# MIET_464512_002_E3_Sheet_1.net
KiCad netlist of a schematic drawn in Altium Designer
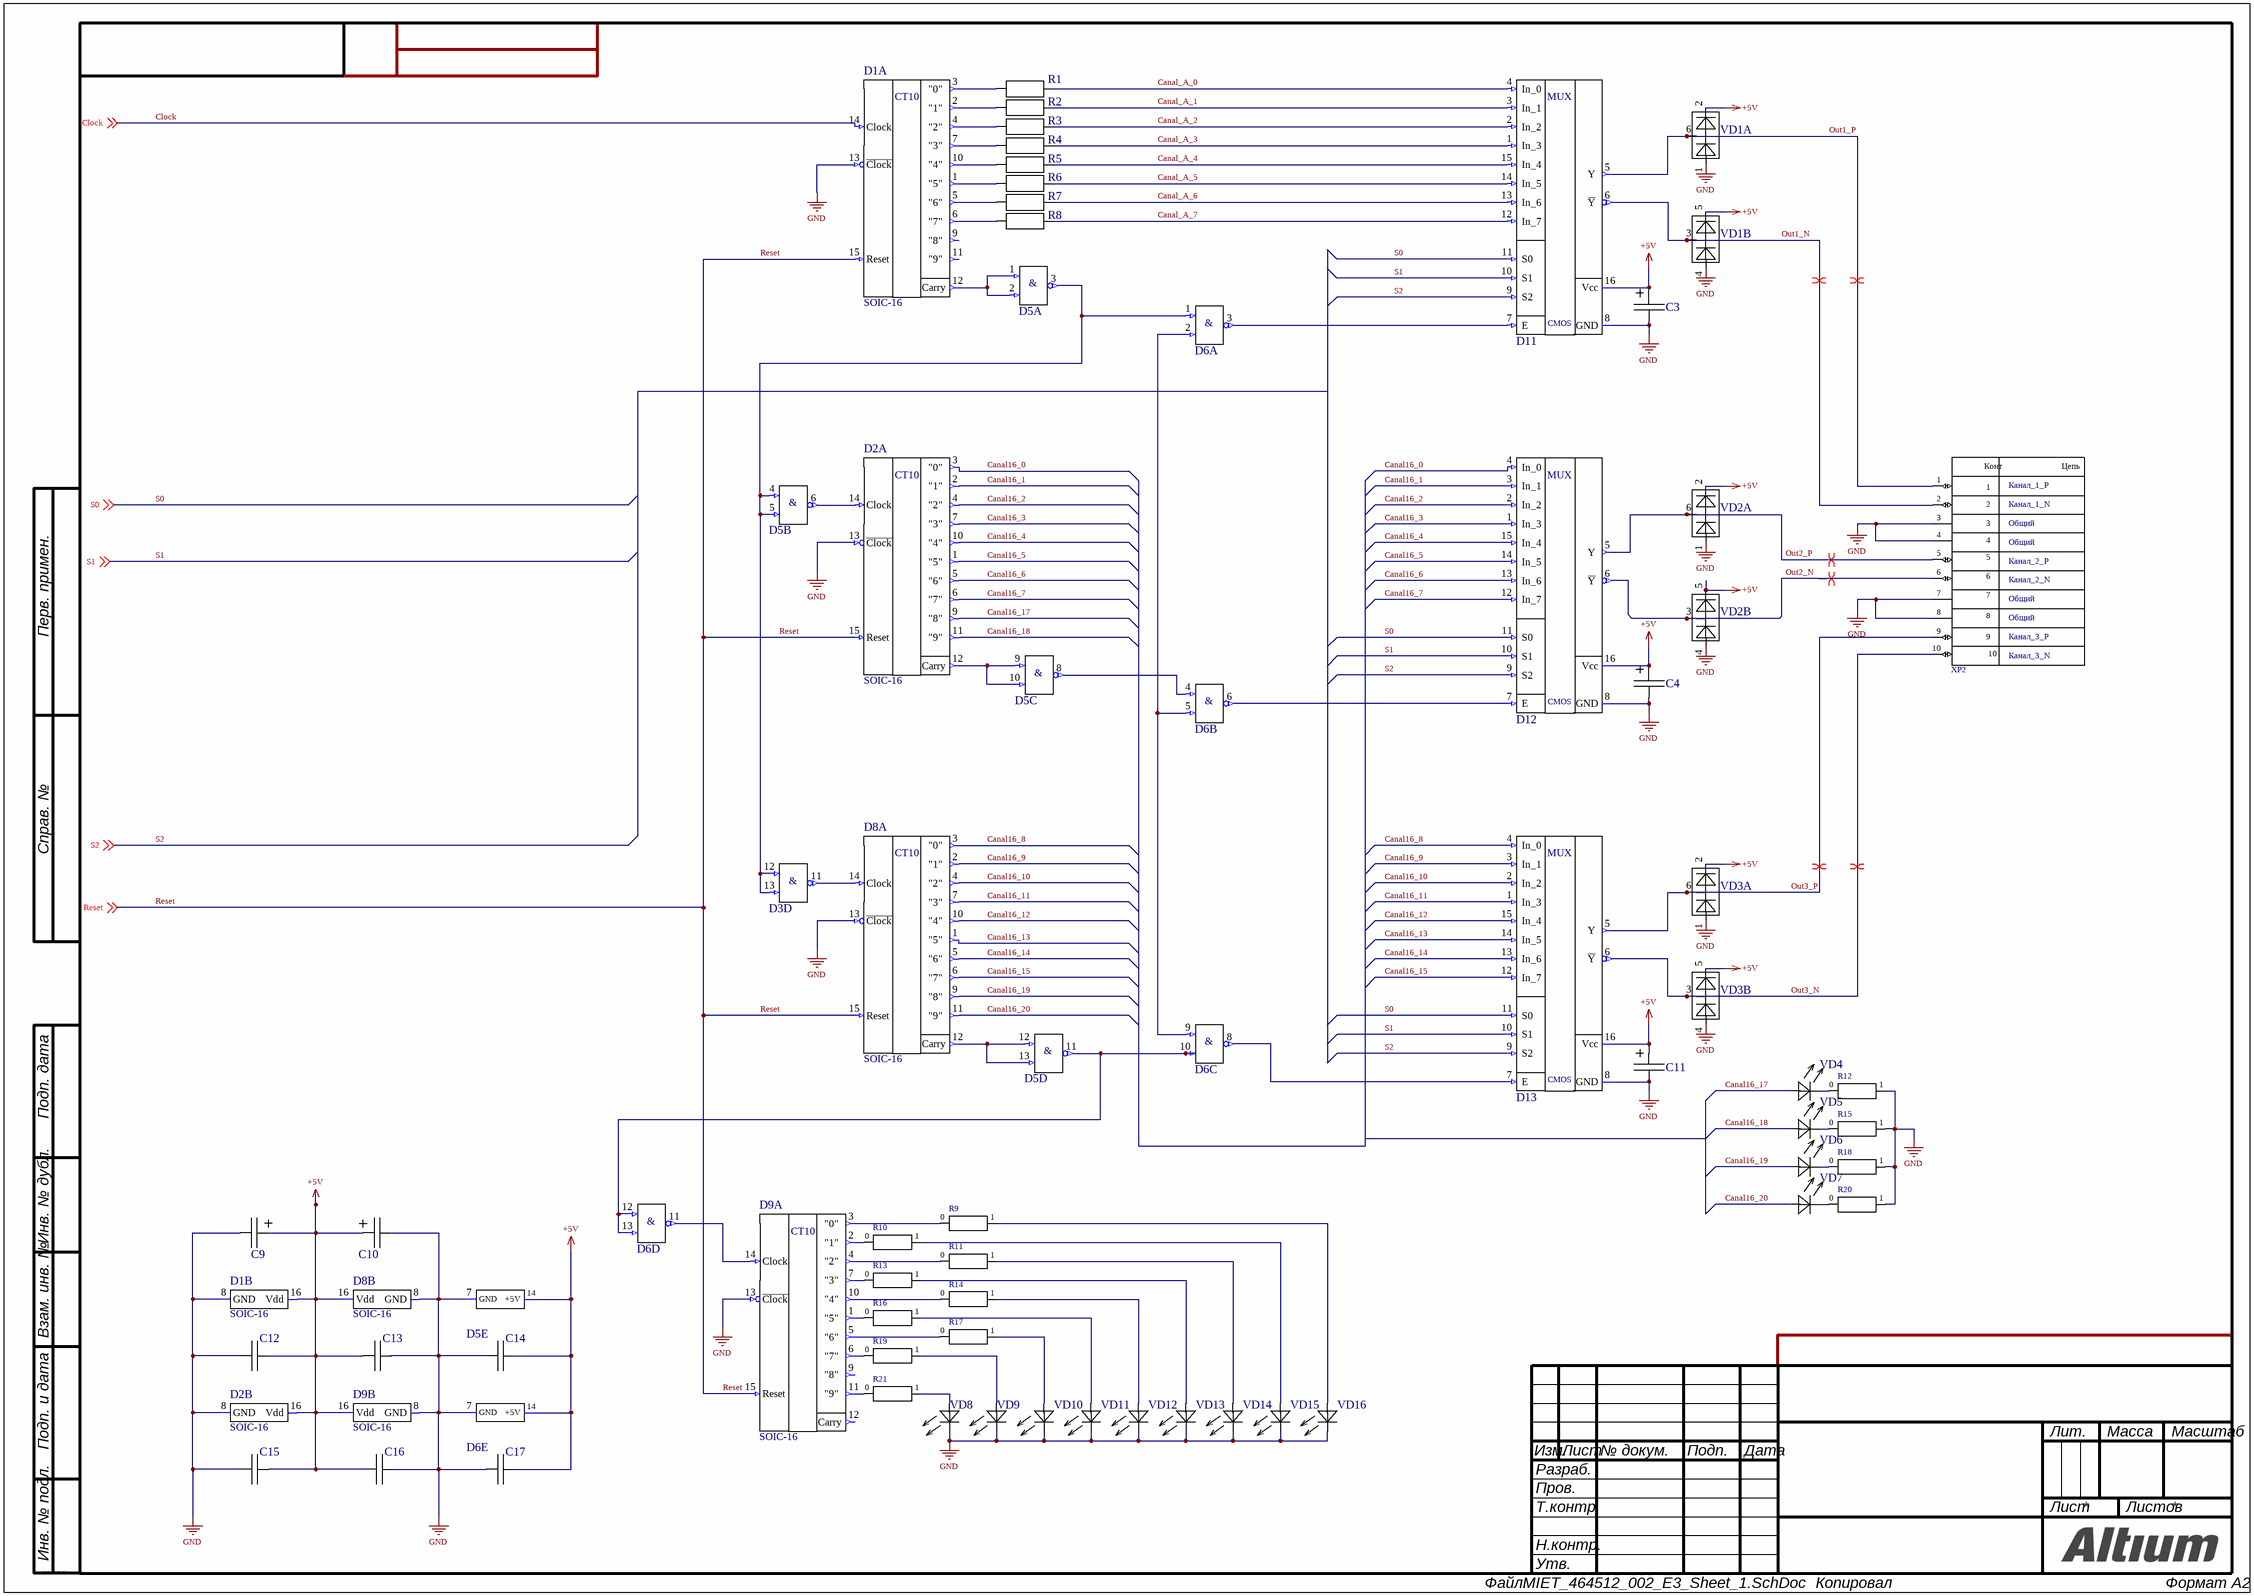
[diagram p0: MIET_464512_002_E3_Sheet_1.SchDoc]

(export (version "E")
  (design (tool "Eeschema 10.0.6"))
  (components
    (comp (ref "C3")
      (value "C")
      (footprint "C-Tantal")
      (description "К53-65 Конденсатор танталовый C(6032) 0,47-100 мкФ")
      (fields
        (field (name "MANUFACTURER") "ОАО \"Элеконд\"")
        (field (name "TOLERANCE") "10%")
        (field (name "CREATED_BY") "Желобаев")
      )
      (libsource (lib "Int_Library_for_Lessons") (part "K53-65_C_10%"))
    )
    (comp (ref "C4")
      (value "C")
      (footprint "C-Tantal")
      (description "К53-65 Конденсатор танталовый C(6032) 0,47-100 мкФ")
      (fields
        (field (name "MANUFACTURER") "ОАО \"Элеконд\"")
        (field (name "TOLERANCE") "10%")
        (field (name "CREATED_BY") "Желобаев")
      )
      (libsource (lib "Int_Library_for_Lessons") (part "K53-65_C_10%"))
    )
    (comp (ref "C9")
      (value "C")
      (footprint "C-Tantal")
      (description "К53-65 Конденсатор танталовый C(6032) 0,47-100 мкФ")
      (fields
        (field (name "MANUFACTURER") "ОАО \"Элеконд\"")
        (field (name "TOLERANCE") "10%")
        (field (name "CREATED_BY") "Желобаев")
      )
      (libsource (lib "Int_Library_for_Lessons") (part "K53-65_C_10%"))
    )
    (comp (ref "C10")
      (value "C")
      (footprint "C-Tantal")
      (description "К53-65 Конденсатор танталовый C(6032) 0,47-100 мкФ")
      (fields
        (field (name "MANUFACTURER") "ОАО \"Элеконд\"")
        (field (name "TOLERANCE") "10%")
        (field (name "CREATED_BY") "Желобаев")
      )
      (libsource (lib "Int_Library_for_Lessons") (part "K53-65_C_10%"))
    )
    (comp (ref "C11")
      (value "C")
      (footprint "C-Tantal")
      (description "К53-65 Конденсатор танталовый C(6032) 0,47-100 мкФ")
      (fields
        (field (name "MANUFACTURER") "ОАО \"Элеконд\"")
        (field (name "TOLERANCE") "10%")
        (field (name "CREATED_BY") "Желобаев")
      )
      (libsource (lib "Int_Library_for_Lessons") (part "K53-65_C_10%"))
    )
    (comp (ref "C12")
      (value "~")
      (footprint "0805_N")
      (description "Чип конденсатор 0805 Н90 ряд Е6")
      (fields
        (field (name "MANUFACTURER") "ООО \"Кулон\"")
        (field (name "TOLERANCE") "+80%-20%")
        (field (name "CREATED_BY") "Желобаев")
      )
      (libsource (lib "Int_Library_for_Lessons") (part "К10-79_0805_Н90"))
    )
    (comp (ref "C13")
      (value "~")
      (footprint "0805_N")
      (description "Чип конденсатор 0805 Н90 ряд Е6")
      (fields
        (field (name "MANUFACTURER") "ООО \"Кулон\"")
        (field (name "TOLERANCE") "+80%-20%")
        (field (name "CREATED_BY") "Желобаев")
      )
      (libsource (lib "Int_Library_for_Lessons") (part "К10-79_0805_Н90"))
    )
    (comp (ref "C14")
      (value "~")
      (footprint "0805_N")
      (description "Чип конденсатор 0805 Н90 ряд Е6")
      (fields
        (field (name "MANUFACTURER") "ООО \"Кулон\"")
        (field (name "TOLERANCE") "+80%-20%")
        (field (name "CREATED_BY") "Желобаев")
      )
      (libsource (lib "Int_Library_for_Lessons") (part "К10-79_0805_Н90"))
    )
    (comp (ref "C15")
      (value "~")
      (footprint "0805_N")
      (description "Чип конденсатор 0805 Н90 ряд Е6")
      (fields
        (field (name "MANUFACTURER") "ООО \"Кулон\"")
        (field (name "TOLERANCE") "+80%-20%")
        (field (name "CREATED_BY") "Желобаев")
      )
      (libsource (lib "Int_Library_for_Lessons") (part "К10-79_0805_Н90"))
    )
    (comp (ref "C16")
      (value "~")
      (footprint "0805_N")
      (description "Чип конденсатор 0805 Н90 ряд Е6")
      (fields
        (field (name "MANUFACTURER") "ООО \"Кулон\"")
        (field (name "TOLERANCE") "+80%-20%")
        (field (name "CREATED_BY") "Желобаев")
      )
      (libsource (lib "Int_Library_for_Lessons") (part "К10-79_0805_Н90"))
    )
    (comp (ref "C17")
      (value "~")
      (footprint "0805_N")
      (description "Чип конденсатор 0805 Н90 ряд Е6")
      (fields
        (field (name "MANUFACTURER") "ООО \"Кулон\"")
        (field (name "TOLERANCE") "+80%-20%")
        (field (name "CREATED_BY") "Желобаев")
      )
      (libsource (lib "Int_Library_for_Lessons") (part "К10-79_0805_Н90"))
    )
    (comp (ref "D1")
      (value "SOIC-16")
      (footprint "SO16-N")
      (description "Декадный счетчик c 10 декодированными выходами")
      (fields (field (name "MANUFACTURER") "STMicroelectronics") (field (name "CREATED_BY") "Желобаев"))
      (libsource (lib "Int_Library_for_Lessons") (part "HCF4017BM1"))
    )
    (comp (ref "D2")
      (value "SOIC-16")
      (footprint "SO16-N")
      (description "Декадный счетчик c 10 декодированными выходами")
      (fields (field (name "MANUFACTURER") "STMicroelectronics") (field (name "CREATED_BY") "Желобаев"))
      (libsource (lib "Int_Library_for_Lessons") (part "HCF4017BM1"))
    )
    (comp (ref "D3")
      (value "74AC00PC")
      (footprint "DIP14")
      (description "4 элемента 2И-НЕ TTL PDIP-14")
      (fields (field (name "MANUFACTURER") "ON Semiconductor") (field (name "CREATED_BY") "Желобаев"))
      (libsource (lib "Int_Library_for_Lessons") (part "74AC00PC"))
    )
    (comp (ref "D5")
      (value "74AC00PC")
      (footprint "DIP14")
      (description "4 элемента 2И-НЕ TTL PDIP-14")
      (fields (field (name "MANUFACTURER") "ON Semiconductor") (field (name "CREATED_BY") "Желобаев"))
      (libsource (lib "Int_Library_for_Lessons") (part "74AC00PC"))
    )
    (comp (ref "D6")
      (value "74AC00PC")
      (footprint "DIP14")
      (description "4 элемента 2И-НЕ TTL PDIP-14")
      (fields (field (name "MANUFACTURER") "ON Semiconductor") (field (name "CREATED_BY") "Желобаев"))
      (libsource (lib "Int_Library_for_Lessons") (part "74AC00PC"))
    )
    (comp (ref "D8")
      (value "SOIC-16")
      (footprint "SO16-N")
      (description "Декадный счетчик c 10 декодированными выходами")
      (fields (field (name "MANUFACTURER") "STMicroelectronics") (field (name "CREATED_BY") "Желобаев"))
      (libsource (lib "Int_Library_for_Lessons") (part "HCF4017BM1"))
    )
    (comp (ref "D9")
      (value "SOIC-16")
      (footprint "SO16-N")
      (description "Декадный счетчик c 10 декодированными выходами")
      (fields (field (name "MANUFACTURER") "STMicroelectronics") (field (name "CREATED_BY") "Желобаев"))
      (libsource (lib "Int_Library_for_Lessons") (part "HCF4017BM1"))
    )
    (comp (ref "D11")
      (value "DIP-16")
      (footprint "DIP16")
      (description "мультиплексор 8 канальный CMOS")
      (fields (field (name "MANUFACTURER") "NXP Semiconductors") (field (name "CREATED_BY") "Желобаев"))
      (libsource (lib "Int_Library_for_Lessons") (part "74HC151N"))
    )
    (comp (ref "D12")
      (value "DIP-16")
      (footprint "DIP16")
      (description "мультиплексор 8 канальный CMOS")
      (fields (field (name "MANUFACTURER") "NXP Semiconductors") (field (name "CREATED_BY") "Желобаев"))
      (libsource (lib "Int_Library_for_Lessons") (part "74HC151N"))
    )
    (comp (ref "D13")
      (value "DIP-16")
      (footprint "DIP16")
      (description "мультиплексор 8 канальный CMOS")
      (fields (field (name "MANUFACTURER") "NXP Semiconductors") (field (name "CREATED_BY") "Желобаев"))
      (libsource (lib "Int_Library_for_Lessons") (part "74HC151N"))
    )
    (comp (ref "R1")
      (value "0805")
      (footprint "RES_0805_2012_N")
      (description "Резистор от 0,75 Ом до 2 МОм")
      (fields
        (field (name "MANUFACTURER") "ОАО \"НПО \"Эркон\"")
        (field (name "TOLERANCE") "5%")
        (field (name "CREATED_BY") "Желобаев")
      )
      (libsource (lib "Int_Library_for_Lessons") (part "Р1-12-0,125-5%"))
    )
    (comp (ref "R2")
      (value "0805")
      (footprint "RES_0805_2012_N")
      (description "Резистор от 0,75 Ом до 2 МОм")
      (fields
        (field (name "MANUFACTURER") "ОАО \"НПО \"Эркон\"")
        (field (name "TOLERANCE") "5%")
        (field (name "CREATED_BY") "Желобаев")
      )
      (libsource (lib "Int_Library_for_Lessons") (part "Р1-12-0,125-5%"))
    )
    (comp (ref "R3")
      (value "0805")
      (footprint "RES_0805_2012_N")
      (description "Резистор от 0,75 Ом до 2 МОм")
      (fields
        (field (name "MANUFACTURER") "ОАО \"НПО \"Эркон\"")
        (field (name "TOLERANCE") "5%")
        (field (name "CREATED_BY") "Желобаев")
      )
      (libsource (lib "Int_Library_for_Lessons") (part "Р1-12-0,125-5%"))
    )
    (comp (ref "R4")
      (value "0805")
      (footprint "RES_0805_2012_N")
      (description "Резистор от 0,75 Ом до 2 МОм")
      (fields
        (field (name "MANUFACTURER") "ОАО \"НПО \"Эркон\"")
        (field (name "TOLERANCE") "5%")
        (field (name "CREATED_BY") "Желобаев")
      )
      (libsource (lib "Int_Library_for_Lessons") (part "Р1-12-0,125-5%"))
    )
    (comp (ref "R5")
      (value "0805")
      (footprint "RES_0805_2012_N")
      (description "Резистор от 0,75 Ом до 2 МОм")
      (fields
        (field (name "MANUFACTURER") "ОАО \"НПО \"Эркон\"")
        (field (name "TOLERANCE") "5%")
        (field (name "CREATED_BY") "Желобаев")
      )
      (libsource (lib "Int_Library_for_Lessons") (part "Р1-12-0,125-5%"))
    )
    (comp (ref "R6")
      (value "0805")
      (footprint "RES_0805_2012_N")
      (description "Резистор от 0,75 Ом до 2 МОм")
      (fields
        (field (name "MANUFACTURER") "ОАО \"НПО \"Эркон\"")
        (field (name "TOLERANCE") "5%")
        (field (name "CREATED_BY") "Желобаев")
      )
      (libsource (lib "Int_Library_for_Lessons") (part "Р1-12-0,125-5%"))
    )
    (comp (ref "R7")
      (value "0805")
      (footprint "RES_0805_2012_N")
      (description "Резистор от 0,75 Ом до 2 МОм")
      (fields
        (field (name "MANUFACTURER") "ОАО \"НПО \"Эркон\"")
        (field (name "TOLERANCE") "5%")
        (field (name "CREATED_BY") "Желобаев")
      )
      (libsource (lib "Int_Library_for_Lessons") (part "Р1-12-0,125-5%"))
    )
    (comp (ref "R8")
      (value "0805")
      (footprint "RES_0805_2012_N")
      (description "Резистор от 0,75 Ом до 2 МОм")
      (fields
        (field (name "MANUFACTURER") "ОАО \"НПО \"Эркон\"")
        (field (name "TOLERANCE") "5%")
        (field (name "CREATED_BY") "Желобаев")
      )
      (libsource (lib "Int_Library_for_Lessons") (part "Р1-12-0,125-5%"))
    )
    (comp (ref "R9")
      (value "P1-12-0,25-5%")
      (footprint "RES_1206")
      (description "Резистор 270 Ом M-\"A\" АЛЯР.434110.005 ТУ")
      (fields
        (field (name "MANUFACTURER") "ОАО \"КБ \"ИКАР\"\"")
        (field (name "TOLERANCE") "5%")
        (field (name "CREATED_BY") "Сарынина")
      )
      (libsource (lib "доп_элементы") (part "P1-12-0,25-5%"))
    )
    (comp (ref "R10")
      (value "P1-12-0,25-5%")
      (footprint "RES_1206")
      (description "Резистор 270 Ом M-\"A\" АЛЯР.434110.005 ТУ")
      (fields
        (field (name "MANUFACTURER") "ОАО \"КБ \"ИКАР\"\"")
        (field (name "TOLERANCE") "5%")
        (field (name "CREATED_BY") "Сарынина")
      )
      (libsource (lib "доп_элементы") (part "P1-12-0,25-5%"))
    )
    (comp (ref "R11")
      (value "P1-12-0,25-5%")
      (footprint "RES_1206")
      (description "Резистор 270 Ом M-\"A\" АЛЯР.434110.005 ТУ")
      (fields
        (field (name "MANUFACTURER") "ОАО \"КБ \"ИКАР\"\"")
        (field (name "TOLERANCE") "5%")
        (field (name "CREATED_BY") "Сарынина")
      )
      (libsource (lib "доп_элементы") (part "P1-12-0,25-5%"))
    )
    (comp (ref "R12")
      (value "P1-12-0,25-5%")
      (footprint "RES_1206")
      (description "Резистор 270 Ом M-\"A\" АЛЯР.434110.005 ТУ")
      (fields
        (field (name "MANUFACTURER") "ОАО \"КБ \"ИКАР\"\"")
        (field (name "TOLERANCE") "5%")
        (field (name "CREATED_BY") "Сарынина")
      )
      (libsource (lib "доп_элементы") (part "P1-12-0,25-5%"))
    )
    (comp (ref "R13")
      (value "P1-12-0,25-5%")
      (footprint "RES_1206")
      (description "Резистор 270 Ом M-\"A\" АЛЯР.434110.005 ТУ")
      (fields
        (field (name "MANUFACTURER") "ОАО \"КБ \"ИКАР\"\"")
        (field (name "TOLERANCE") "5%")
        (field (name "CREATED_BY") "Сарынина")
      )
      (libsource (lib "доп_элементы") (part "P1-12-0,25-5%"))
    )
    (comp (ref "R14")
      (value "P1-12-0,25-5%")
      (footprint "RES_1206")
      (description "Резистор 270 Ом M-\"A\" АЛЯР.434110.005 ТУ")
      (fields
        (field (name "MANUFACTURER") "ОАО \"КБ \"ИКАР\"\"")
        (field (name "TOLERANCE") "5%")
        (field (name "CREATED_BY") "Сарынина")
      )
      (libsource (lib "доп_элементы") (part "P1-12-0,25-5%"))
    )
    (comp (ref "R15")
      (value "P1-12-0,25-5%")
      (footprint "RES_1206")
      (description "Резистор 270 Ом M-\"A\" АЛЯР.434110.005 ТУ")
      (fields
        (field (name "MANUFACTURER") "ОАО \"КБ \"ИКАР\"\"")
        (field (name "TOLERANCE") "5%")
        (field (name "CREATED_BY") "Сарынина")
      )
      (libsource (lib "доп_элементы") (part "P1-12-0,25-5%"))
    )
    (comp (ref "R16")
      (value "P1-12-0,25-5%")
      (footprint "RES_1206")
      (description "Резистор 270 Ом M-\"A\" АЛЯР.434110.005 ТУ")
      (fields
        (field (name "MANUFACTURER") "ОАО \"КБ \"ИКАР\"\"")
        (field (name "TOLERANCE") "5%")
        (field (name "CREATED_BY") "Сарынина")
      )
      (libsource (lib "доп_элементы") (part "P1-12-0,25-5%"))
    )
    (comp (ref "R17")
      (value "P1-12-0,25-5%")
      (footprint "RES_1206")
      (description "Резистор 270 Ом M-\"A\" АЛЯР.434110.005 ТУ")
      (fields
        (field (name "MANUFACTURER") "ОАО \"КБ \"ИКАР\"\"")
        (field (name "TOLERANCE") "5%")
        (field (name "CREATED_BY") "Сарынина")
      )
      (libsource (lib "доп_элементы") (part "P1-12-0,25-5%"))
    )
    (comp (ref "R18")
      (value "P1-12-0,25-5%")
      (footprint "RES_1206")
      (description "Резистор 270 Ом M-\"A\" АЛЯР.434110.005 ТУ")
      (fields
        (field (name "MANUFACTURER") "ОАО \"КБ \"ИКАР\"\"")
        (field (name "TOLERANCE") "5%")
        (field (name "CREATED_BY") "Сарынина")
      )
      (libsource (lib "доп_элементы") (part "P1-12-0,25-5%"))
    )
    (comp (ref "R19")
      (value "P1-12-0,25-5%")
      (footprint "RES_1206")
      (description "Резистор 270 Ом M-\"A\" АЛЯР.434110.005 ТУ")
      (fields
        (field (name "MANUFACTURER") "ОАО \"КБ \"ИКАР\"\"")
        (field (name "TOLERANCE") "5%")
        (field (name "CREATED_BY") "Сарынина")
      )
      (libsource (lib "доп_элементы") (part "P1-12-0,25-5%"))
    )
    (comp (ref "R20")
      (value "P1-12-0,25-5%")
      (footprint "RES_1206")
      (description "Резистор 270 Ом M-\"A\" АЛЯР.434110.005 ТУ")
      (fields
        (field (name "MANUFACTURER") "ОАО \"КБ \"ИКАР\"\"")
        (field (name "TOLERANCE") "5%")
        (field (name "CREATED_BY") "Сарынина")
      )
      (libsource (lib "доп_элементы") (part "P1-12-0,25-5%"))
    )
    (comp (ref "R21")
      (value "P1-12-0,25-5%")
      (footprint "RES_1206")
      (description "Резистор 270 Ом M-\"A\" АЛЯР.434110.005 ТУ")
      (fields
        (field (name "MANUFACTURER") "ОАО \"КБ \"ИКАР\"\"")
        (field (name "TOLERANCE") "5%")
        (field (name "CREATED_BY") "Сарынина")
      )
      (libsource (lib "доп_элементы") (part "P1-12-0,25-5%"))
    )
    (comp (ref "VD1")
      (value "SOT-363")
      (footprint "SOT363_NXP")
      (description "Высокоскоростные, переключающие диоды")
      (fields
        (field (name "MANUFACTURER") "Nexperia")
        (field (name "VOLTAGE") "100")
        (field (name "CREATED_BY") "Желобаев")
      )
      (libsource (lib "Int_Library_for_Lessons") (part "BAV99S"))
    )
    (comp (ref "VD2")
      (value "SOT-363")
      (footprint "SOT363_NXP")
      (description "Высокоскоростные, переключающие диоды")
      (fields
        (field (name "MANUFACTURER") "Nexperia")
        (field (name "VOLTAGE") "100")
        (field (name "CREATED_BY") "Желобаев")
      )
      (libsource (lib "Int_Library_for_Lessons") (part "BAV99S"))
    )
    (comp (ref "VD3")
      (value "SOT-363")
      (footprint "SOT363_NXP")
      (description "Высокоскоростные, переключающие диоды")
      (fields
        (field (name "MANUFACTURER") "Nexperia")
        (field (name "VOLTAGE") "100")
        (field (name "CREATED_BY") "Желобаев")
      )
      (libsource (lib "Int_Library_for_Lessons") (part "BAV99S"))
    )
    (comp (ref "VD4")
      (value "0805")
      (footprint "0805_LightDiode")
      (description "светодиод 0805 зеленый")
      (fields (field (name "MANUFACTURER") "Kingbright") (field (name "CREATED_BY") "Желобаев"))
      (libsource (lib "Int_Library_for_Lessons") (part "AP2012MGC"))
    )
    (comp (ref "VD5")
      (value "0805")
      (footprint "0805_LightDiode")
      (description "светодиод 0805 зеленый")
      (fields (field (name "MANUFACTURER") "Kingbright") (field (name "CREATED_BY") "Желобаев"))
      (libsource (lib "Int_Library_for_Lessons") (part "AP2012MGC"))
    )
    (comp (ref "VD6")
      (value "0805")
      (footprint "0805_LightDiode")
      (description "светодиод 0805 зеленый")
      (fields (field (name "MANUFACTURER") "Kingbright") (field (name "CREATED_BY") "Желобаев"))
      (libsource (lib "Int_Library_for_Lessons") (part "AP2012MGC"))
    )
    (comp (ref "VD7")
      (value "0805")
      (footprint "0805_LightDiode")
      (description "светодиод 0805 зеленый")
      (fields (field (name "MANUFACTURER") "Kingbright") (field (name "CREATED_BY") "Желобаев"))
      (libsource (lib "Int_Library_for_Lessons") (part "AP2012MGC"))
    )
    (comp (ref "VD8")
      (value "0805")
      (footprint "0805_LightDiode")
      (description "светодиод 0805 красный")
      (fields (field (name "MANUFACTURER") "Kingbright") (field (name "CREATED_BY") "Желобаев"))
      (libsource (lib "Int_Library_for_Lessons") (part "AP2012EC"))
    )
    (comp (ref "VD9")
      (value "0805")
      (footprint "0805_LightDiode")
      (description "светодиод 0805 зеленый")
      (fields (field (name "MANUFACTURER") "Kingbright") (field (name "CREATED_BY") "Желобаев"))
      (libsource (lib "Int_Library_for_Lessons") (part "AP2012MGC"))
    )
    (comp (ref "VD10")
      (value "0805")
      (footprint "0805_LightDiode")
      (description "светодиод 0805 зеленый")
      (fields (field (name "MANUFACTURER") "Kingbright") (field (name "CREATED_BY") "Желобаев"))
      (libsource (lib "Int_Library_for_Lessons") (part "AP2012MGC"))
    )
    (comp (ref "VD11")
      (value "0805")
      (footprint "0805_LightDiode")
      (description "светодиод 0805 зеленый")
      (fields (field (name "MANUFACTURER") "Kingbright") (field (name "CREATED_BY") "Желобаев"))
      (libsource (lib "Int_Library_for_Lessons") (part "AP2012MGC"))
    )
    (comp (ref "VD12")
      (value "0805")
      (footprint "0805_LightDiode")
      (description "светодиод 0805 зеленый")
      (fields (field (name "MANUFACTURER") "Kingbright") (field (name "CREATED_BY") "Желобаев"))
      (libsource (lib "Int_Library_for_Lessons") (part "AP2012MGC"))
    )
    (comp (ref "VD13")
      (value "0805")
      (footprint "0805_LightDiode")
      (description "светодиод 0805 зеленый")
      (fields (field (name "MANUFACTURER") "Kingbright") (field (name "CREATED_BY") "Желобаев"))
      (libsource (lib "Int_Library_for_Lessons") (part "AP2012MGC"))
    )
    (comp (ref "VD14")
      (value "0805")
      (footprint "0805_LightDiode")
      (description "светодиод 0805 зеленый")
      (fields (field (name "MANUFACTURER") "Kingbright") (field (name "CREATED_BY") "Желобаев"))
      (libsource (lib "Int_Library_for_Lessons") (part "AP2012MGC"))
    )
    (comp (ref "VD15")
      (value "0805")
      (footprint "0805_LightDiode")
      (description "светодиод 0805 зеленый")
      (fields (field (name "MANUFACTURER") "Kingbright") (field (name "CREATED_BY") "Желобаев"))
      (libsource (lib "Int_Library_for_Lessons") (part "AP2012MGC"))
    )
    (comp (ref "VD16")
      (value "0805")
      (footprint "0805_LightDiode")
      (description "светодиод 0805 зеленый")
      (fields (field (name "MANUFACTURER") "Kingbright") (field (name "CREATED_BY") "Желобаев"))
      (libsource (lib "Int_Library_for_Lessons") (part "AP2012MGC"))
    )
    (comp (ref "XP2")
      (value "TE_1-1634688-0 \"TE Connectivity\"")
      (footprint "TE_1-1634688-0_IDC10_V")
      (description "Вилка прямая")
      (libsource (lib "доп_элементы") (part "TE_1-1634688-0 {dblquote}TE Connectivity{dblquote}"))
    )
  )
  (nets
    (net (code "1") (name "+5V") (class "Default")
      (node (ref "C10") (pin "+") (pinfunction "+_+") (pintype "passive"))
      (node (ref "C11") (pin "+") (pinfunction "+_+") (pintype "passive"))
      (node (ref "C12") (pin "2") (pinfunction "2_2") (pintype "passive"))
      (node (ref "C13") (pin "1") (pinfunction "1_1") (pintype "passive"))
      (node (ref "C14") (pin "2") (pinfunction "2_2") (pintype "passive"))
      (node (ref "C15") (pin "2") (pinfunction "2_2") (pintype "passive"))
      (node (ref "C16") (pin "1") (pinfunction "1_1") (pintype "passive"))
      (node (ref "C17") (pin "2") (pinfunction "2_2") (pintype "passive"))
      (node (ref "C3") (pin "+") (pinfunction "+_+") (pintype "passive"))
      (node (ref "C4") (pin "+") (pinfunction "+_+") (pintype "passive"))
      (node (ref "C9") (pin "+") (pinfunction "+_+") (pintype "passive"))
      (node (ref "D1") (pin "16") (pinfunction "Vdd_16") (pintype "power_in"))
      (node (ref "D11") (pin "16") (pinfunction "Vcc_16") (pintype "power_in"))
      (node (ref "D12") (pin "16") (pinfunction "Vcc_16") (pintype "power_in"))
      (node (ref "D13") (pin "16") (pinfunction "Vcc_16") (pintype "power_in"))
      (node (ref "D2") (pin "16") (pinfunction "Vdd_16") (pintype "power_in"))
      (node (ref "D5") (pin "14") (pinfunction "+5V_14") (pintype "power_in"))
      (node (ref "D6") (pin "14") (pinfunction "+5V_14") (pintype "power_in"))
      (node (ref "D8") (pin "16") (pinfunction "Vdd_16") (pintype "power_in"))
      (node (ref "D9") (pin "16") (pinfunction "Vdd_16") (pintype "power_in"))
      (node (ref "VD1") (pin "2") (pinfunction "K2_2") (pintype "passive"))
      (node (ref "VD1") (pin "5") (pinfunction "K4_5") (pintype "passive"))
      (node (ref "VD2") (pin "2") (pinfunction "K2_2") (pintype "passive"))
      (node (ref "VD2") (pin "5") (pinfunction "K4_5") (pintype "passive"))
      (node (ref "VD3") (pin "2") (pinfunction "K2_2") (pintype "passive"))
      (node (ref "VD3") (pin "5") (pinfunction "K4_5") (pintype "passive"))
    )
    (net (code "2") (name "/Canal16_0") (class "Default")
      (node (ref "D12") (pin "4") (pinfunction "In_0_4") (pintype "input"))
      (node (ref "D2") (pin "3") (pinfunction "\"0\"_3") (pintype "output"))
    )
    (net (code "3") (name "/Canal16_1") (class "Default")
      (node (ref "D12") (pin "3") (pinfunction "In_1_3") (pintype "input"))
      (node (ref "D2") (pin "2") (pinfunction "\"1\"_2") (pintype "output"))
    )
    (net (code "4") (name "/Canal16_2") (class "Default")
      (node (ref "D12") (pin "2") (pinfunction "In_2_2") (pintype "input"))
      (node (ref "D2") (pin "4") (pinfunction "\"2\"_4") (pintype "output"))
    )
    (net (code "5") (name "/Canal16_3") (class "Default")
      (node (ref "D12") (pin "1") (pinfunction "In_3_1") (pintype "input"))
      (node (ref "D2") (pin "7") (pinfunction "\"3\"_7") (pintype "output"))
    )
    (net (code "6") (name "/Canal16_4") (class "Default")
      (node (ref "D12") (pin "15") (pinfunction "In_4_15") (pintype "input"))
      (node (ref "D2") (pin "10") (pinfunction "\"4\"_10") (pintype "output"))
    )
    (net (code "7") (name "/Canal16_5") (class "Default")
      (node (ref "D12") (pin "14") (pinfunction "In_5_14") (pintype "input"))
      (node (ref "D2") (pin "1") (pinfunction "\"5\"_1") (pintype "output"))
    )
    (net (code "8") (name "/Canal16_6") (class "Default")
      (node (ref "D12") (pin "13") (pinfunction "In_6_13") (pintype "input"))
      (node (ref "D2") (pin "5") (pinfunction "\"6\"_5") (pintype "output"))
    )
    (net (code "9") (name "/Canal16_7") (class "Default")
      (node (ref "D12") (pin "12") (pinfunction "In_7_12") (pintype "input"))
      (node (ref "D2") (pin "6") (pinfunction "\"7\"_6") (pintype "output"))
    )
    (net (code "10") (name "/Canal16_8") (class "Default")
      (node (ref "D13") (pin "4") (pinfunction "In_0_4") (pintype "input"))
      (node (ref "D8") (pin "3") (pinfunction "\"0\"_3") (pintype "output"))
    )
    (net (code "11") (name "/Canal16_9") (class "Default")
      (node (ref "D13") (pin "3") (pinfunction "In_1_3") (pintype "input"))
      (node (ref "D8") (pin "2") (pinfunction "\"1\"_2") (pintype "output"))
    )
    (net (code "12") (name "/Canal16_10") (class "Default")
      (node (ref "D13") (pin "2") (pinfunction "In_2_2") (pintype "input"))
      (node (ref "D8") (pin "4") (pinfunction "\"2\"_4") (pintype "output"))
    )
    (net (code "13") (name "/Canal16_11") (class "Default")
      (node (ref "D13") (pin "1") (pinfunction "In_3_1") (pintype "input"))
      (node (ref "D8") (pin "7") (pinfunction "\"3\"_7") (pintype "output"))
    )
    (net (code "14") (name "/Canal16_12") (class "Default")
      (node (ref "D13") (pin "15") (pinfunction "In_4_15") (pintype "input"))
      (node (ref "D8") (pin "10") (pinfunction "\"4\"_10") (pintype "output"))
    )
    (net (code "15") (name "/Canal16_13") (class "Default")
      (node (ref "D13") (pin "14") (pinfunction "In_5_14") (pintype "input"))
      (node (ref "D8") (pin "1") (pinfunction "\"5\"_1") (pintype "output"))
    )
    (net (code "16") (name "/Canal16_14") (class "Default")
      (node (ref "D13") (pin "13") (pinfunction "In_6_13") (pintype "input"))
      (node (ref "D8") (pin "5") (pinfunction "\"6\"_5") (pintype "output"))
    )
    (net (code "17") (name "/Canal16_15") (class "Default")
      (node (ref "D13") (pin "12") (pinfunction "In_7_12") (pintype "input"))
      (node (ref "D8") (pin "6") (pinfunction "\"7\"_6") (pintype "output"))
    )
    (net (code "18") (name "/Canal16_17") (class "Default")
      (node (ref "D2") (pin "9") (pinfunction "\"8\"_9") (pintype "output"))
      (node (ref "VD4") (pin "A") (pinfunction "A_A") (pintype "passive"))
    )
    (net (code "19") (name "/Canal16_18") (class "Default")
      (node (ref "D2") (pin "11") (pinfunction "\"9\"_11") (pintype "output"))
      (node (ref "VD5") (pin "A") (pinfunction "A_A") (pintype "passive"))
    )
    (net (code "20") (name "/Canal16_19") (class "Default")
      (node (ref "D8") (pin "9") (pinfunction "\"8\"_9") (pintype "output"))
      (node (ref "VD6") (pin "A") (pinfunction "A_A") (pintype "passive"))
    )
    (net (code "21") (name "/Canal16_20") (class "Default")
      (node (ref "D8") (pin "11") (pinfunction "\"9\"_11") (pintype "output"))
      (node (ref "VD7") (pin "A") (pinfunction "A_A") (pintype "passive"))
    )
    (net (code "22") (name "/Canal_A_0") (class "Default")
      (node (ref "D11") (pin "4") (pinfunction "In_0_4") (pintype "input"))
      (node (ref "R1") (pin "2") (pinfunction "2_2") (pintype "passive"))
    )
    (net (code "23") (name "/Canal_A_1") (class "Default")
      (node (ref "D11") (pin "3") (pinfunction "In_1_3") (pintype "input"))
      (node (ref "R2") (pin "2") (pinfunction "2_2") (pintype "passive"))
    )
    (net (code "24") (name "/Canal_A_2") (class "Default")
      (node (ref "D11") (pin "2") (pinfunction "In_2_2") (pintype "input"))
      (node (ref "R3") (pin "2") (pinfunction "2_2") (pintype "passive"))
    )
    (net (code "25") (name "/Canal_A_3") (class "Default")
      (node (ref "D11") (pin "1") (pinfunction "In_3_1") (pintype "input"))
      (node (ref "R4") (pin "2") (pinfunction "2_2") (pintype "passive"))
    )
    (net (code "26") (name "/Canal_A_4") (class "Default")
      (node (ref "D11") (pin "15") (pinfunction "In_4_15") (pintype "input"))
      (node (ref "R5") (pin "2") (pinfunction "2_2") (pintype "passive"))
    )
    (net (code "27") (name "/Canal_A_5") (class "Default")
      (node (ref "D11") (pin "14") (pinfunction "In_5_14") (pintype "input"))
      (node (ref "R6") (pin "2") (pinfunction "2_2") (pintype "passive"))
    )
    (net (code "28") (name "/Canal_A_6") (class "Default")
      (node (ref "D11") (pin "13") (pinfunction "In_6_13") (pintype "input"))
      (node (ref "R7") (pin "2") (pinfunction "2_2") (pintype "passive"))
    )
    (net (code "29") (name "/Canal_A_7") (class "Default")
      (node (ref "D11") (pin "12") (pinfunction "In_7_12") (pintype "input"))
      (node (ref "R8") (pin "2") (pinfunction "2_2") (pintype "passive"))
    )
    (net (code "30") (name "/Out1_N") (class "Default")
      (node (ref "D11") (pin "6") (pinfunction "Y_6") (pintype "output"))
      (node (ref "VD1") (pin "3") (pinfunction "K3A4_3") (pintype "passive"))
      (node (ref "XP2") (pin "2") (pinfunction "39_2") (pintype "bidirectional"))
    )
    (net (code "31") (name "/Out1_P") (class "Default")
      (node (ref "D11") (pin "5") (pinfunction "Y_5") (pintype "output"))
      (node (ref "VD1") (pin "6") (pinfunction "K1A2_6") (pintype "passive"))
      (node (ref "XP2") (pin "1") (pinfunction "38_1") (pintype "bidirectional"))
    )
    (net (code "32") (name "/Out2_N") (class "Default")
      (node (ref "D12") (pin "6") (pinfunction "Y_6") (pintype "output"))
      (node (ref "VD2") (pin "3") (pinfunction "K3A4_3") (pintype "passive"))
      (node (ref "XP2") (pin "6") (pinfunction "43_6") (pintype "bidirectional"))
    )
    (net (code "33") (name "/Out2_P") (class "Default")
      (node (ref "D12") (pin "5") (pinfunction "Y_5") (pintype "output"))
      (node (ref "VD2") (pin "6") (pinfunction "K1A2_6") (pintype "passive"))
      (node (ref "XP2") (pin "5") (pinfunction "42_5") (pintype "bidirectional"))
    )
    (net (code "34") (name "/Out3_N") (class "Default")
      (node (ref "D13") (pin "6") (pinfunction "Y_6") (pintype "output"))
      (node (ref "VD3") (pin "3") (pinfunction "K3A4_3") (pintype "passive"))
      (node (ref "XP2") (pin "10") (pinfunction "47_10") (pintype "bidirectional"))
    )
    (net (code "35") (name "/Out3_P") (class "Default")
      (node (ref "D13") (pin "5") (pinfunction "Y_5") (pintype "output"))
      (node (ref "VD3") (pin "6") (pinfunction "K1A2_6") (pintype "passive"))
      (node (ref "XP2") (pin "9") (pinfunction "46_9") (pintype "bidirectional"))
    )
    (net (code "36") (name "Clock") (class "Default")
      (node (ref "D1") (pin "14") (pinfunction "Clock_14") (pintype "input"))
    )
    (net (code "37") (name "GND") (class "Default")
      (node (ref "C10") (pin "-") (pinfunction "-_-") (pintype "passive"))
      (node (ref "C11") (pin "-") (pinfunction "-_-") (pintype "passive"))
      (node (ref "C12") (pin "1") (pinfunction "1_1") (pintype "passive"))
      (node (ref "C13") (pin "2") (pinfunction "2_2") (pintype "passive"))
      (node (ref "C14") (pin "1") (pinfunction "1_1") (pintype "passive"))
      (node (ref "C15") (pin "1") (pinfunction "1_1") (pintype "passive"))
      (node (ref "C16") (pin "2") (pinfunction "2_2") (pintype "passive"))
      (node (ref "C17") (pin "1") (pinfunction "1_1") (pintype "passive"))
      (node (ref "C3") (pin "-") (pinfunction "-_-") (pintype "passive"))
      (node (ref "C4") (pin "-") (pinfunction "-_-") (pintype "passive"))
      (node (ref "C9") (pin "-") (pinfunction "-_-") (pintype "passive"))
      (node (ref "D1") (pin "13") (pinfunction "Clock_13") (pintype "input"))
      (node (ref "D1") (pin "8") (pinfunction "GND_8") (pintype "power_in"))
      (node (ref "D11") (pin "8") (pinfunction "GND_8") (pintype "power_in"))
      (node (ref "D12") (pin "8") (pinfunction "GND_8") (pintype "power_in"))
      (node (ref "D13") (pin "8") (pinfunction "GND_8") (pintype "power_in"))
      (node (ref "D2") (pin "13") (pinfunction "Clock_13") (pintype "input"))
      (node (ref "D2") (pin "8") (pinfunction "GND_8") (pintype "power_in"))
      (node (ref "D5") (pin "7") (pinfunction "GND_7") (pintype "power_in"))
      (node (ref "D6") (pin "7") (pinfunction "GND_7") (pintype "power_in"))
      (node (ref "D8") (pin "13") (pinfunction "Clock_13") (pintype "input"))
      (node (ref "D8") (pin "8") (pinfunction "GND_8") (pintype "power_in"))
      (node (ref "D9") (pin "13") (pinfunction "Clock_13") (pintype "input"))
      (node (ref "D9") (pin "8") (pinfunction "GND_8") (pintype "power_in"))
      (node (ref "R12") (pin "1") (pinfunction "1_1") (pintype "passive"))
      (node (ref "R15") (pin "1") (pinfunction "1_1") (pintype "passive"))
      (node (ref "R18") (pin "1") (pinfunction "1_1") (pintype "passive"))
      (node (ref "R20") (pin "1") (pinfunction "1_1") (pintype "passive"))
      (node (ref "VD1") (pin "1") (pinfunction "A1_1") (pintype "passive"))
      (node (ref "VD1") (pin "4") (pinfunction "A3_4") (pintype "passive"))
      (node (ref "VD10") (pin "K") (pinfunction "K_K") (pintype "passive"))
      (node (ref "VD11") (pin "K") (pinfunction "K_K") (pintype "passive"))
      (node (ref "VD12") (pin "K") (pinfunction "K_K") (pintype "passive"))
      (node (ref "VD13") (pin "K") (pinfunction "K_K") (pintype "passive"))
      (node (ref "VD14") (pin "K") (pinfunction "K_K") (pintype "passive"))
      (node (ref "VD15") (pin "K") (pinfunction "K_K") (pintype "passive"))
      (node (ref "VD16") (pin "K") (pinfunction "K_K") (pintype "passive"))
      (node (ref "VD2") (pin "1") (pinfunction "A1_1") (pintype "passive"))
      (node (ref "VD2") (pin "4") (pinfunction "A3_4") (pintype "passive"))
      (node (ref "VD3") (pin "1") (pinfunction "A1_1") (pintype "passive"))
      (node (ref "VD3") (pin "4") (pinfunction "A3_4") (pintype "passive"))
      (node (ref "VD8") (pin "K") (pinfunction "K_K") (pintype "passive"))
      (node (ref "VD9") (pin "K") (pinfunction "K_K") (pintype "passive"))
      (node (ref "XP2") (pin "3") (pinfunction "40_3") (pintype "passive"))
      (node (ref "XP2") (pin "4") (pinfunction "41_4") (pintype "passive"))
      (node (ref "XP2") (pin "7") (pinfunction "44_7") (pintype "passive"))
      (node (ref "XP2") (pin "8") (pinfunction "45_8") (pintype "passive"))
    )
    (net (code "38") (name "Net-(D1A-\"0\")") (class "Default")
      (node (ref "D1") (pin "3") (pinfunction "\"0\"_3") (pintype "output"))
      (node (ref "R1") (pin "1") (pinfunction "1_1") (pintype "passive"))
    )
    (net (code "39") (name "Net-(D1A-\"1\")") (class "Default")
      (node (ref "D1") (pin "2") (pinfunction "\"1\"_2") (pintype "output"))
      (node (ref "R2") (pin "1") (pinfunction "1_1") (pintype "passive"))
    )
    (net (code "40") (name "Net-(D1A-\"2\")") (class "Default")
      (node (ref "D1") (pin "4") (pinfunction "\"2\"_4") (pintype "output"))
      (node (ref "R3") (pin "1") (pinfunction "1_1") (pintype "passive"))
    )
    (net (code "41") (name "Net-(D1A-\"3\")") (class "Default")
      (node (ref "D1") (pin "7") (pinfunction "\"3\"_7") (pintype "output"))
      (node (ref "R4") (pin "1") (pinfunction "1_1") (pintype "passive"))
    )
    (net (code "42") (name "Net-(D1A-\"4\")") (class "Default")
      (node (ref "D1") (pin "10") (pinfunction "\"4\"_10") (pintype "output"))
      (node (ref "R5") (pin "1") (pinfunction "1_1") (pintype "passive"))
    )
    (net (code "43") (name "Net-(D1A-\"5\")") (class "Default")
      (node (ref "D1") (pin "1") (pinfunction "\"5\"_1") (pintype "output"))
      (node (ref "R6") (pin "1") (pinfunction "1_1") (pintype "passive"))
    )
    (net (code "44") (name "Net-(D1A-\"6\")") (class "Default")
      (node (ref "D1") (pin "5") (pinfunction "\"6\"_5") (pintype "output"))
      (node (ref "R7") (pin "1") (pinfunction "1_1") (pintype "passive"))
    )
    (net (code "45") (name "Net-(D1A-\"7\")") (class "Default")
      (node (ref "D1") (pin "6") (pinfunction "\"7\"_6") (pintype "output"))
      (node (ref "R8") (pin "1") (pinfunction "1_1") (pintype "passive"))
    )
    (net (code "46") (name "Net-(D1A-Carry)") (class "Default")
      (node (ref "D1") (pin "12") (pinfunction "Carry_12") (pintype "output"))
      (node (ref "D5") (pin "1") (pinfunction "In1_1") (pintype "input"))
      (node (ref "D5") (pin "2") (pinfunction "In2_2") (pintype "input"))
    )
    (net (code "47") (name "Net-(D2A-Carry)") (class "Default")
      (node (ref "D2") (pin "12") (pinfunction "Carry_12") (pintype "output"))
      (node (ref "D5") (pin "10") (pinfunction "In2_10") (pintype "input"))
      (node (ref "D5") (pin "9") (pinfunction "In1_9") (pintype "input"))
    )
    (net (code "48") (name "Net-(D3D-In1)") (class "Default")
      (node (ref "D3") (pin "12") (pinfunction "In1_12") (pintype "input"))
      (node (ref "D3") (pin "13") (pinfunction "In2_13") (pintype "input"))
      (node (ref "D5") (pin "3") (pinfunction "Out_3") (pintype "output"))
      (node (ref "D5") (pin "4") (pinfunction "In1_4") (pintype "input"))
      (node (ref "D5") (pin "5") (pinfunction "In2_5") (pintype "input"))
      (node (ref "D6") (pin "1") (pinfunction "In1_1") (pintype "input"))
    )
    (net (code "49") (name "Net-(D3D-Out)") (class "Default")
      (node (ref "D3") (pin "11") (pinfunction "Out_11") (pintype "output"))
      (node (ref "D8") (pin "14") (pinfunction "Clock_14") (pintype "input"))
    )
    (net (code "50") (name "Net-(D5B-Out)") (class "Default")
      (node (ref "D2") (pin "14") (pinfunction "Clock_14") (pintype "input"))
      (node (ref "D5") (pin "6") (pinfunction "Out_6") (pintype "output"))
    )
    (net (code "51") (name "Net-(D5C-Out)") (class "Default")
      (node (ref "D5") (pin "8") (pinfunction "Out_8") (pintype "output"))
      (node (ref "D6") (pin "4") (pinfunction "In1_4") (pintype "input"))
    )
    (net (code "52") (name "Net-(D5D-In1)") (class "Default")
      (node (ref "D5") (pin "12") (pinfunction "In1_12") (pintype "input"))
      (node (ref "D5") (pin "13") (pinfunction "In2_13") (pintype "input"))
      (node (ref "D8") (pin "12") (pinfunction "Carry_12") (pintype "output"))
    )
    (net (code "53") (name "Net-(D5D-Out)") (class "Default")
      (node (ref "D5") (pin "11") (pinfunction "Out_11") (pintype "output"))
      (node (ref "D6") (pin "10") (pinfunction "In2_10") (pintype "input"))
      (node (ref "D6") (pin "12") (pinfunction "In1_12") (pintype "input"))
      (node (ref "D6") (pin "13") (pinfunction "In2_13") (pintype "input"))
    )
    (net (code "54") (name "Net-(D6A-In2)") (class "Default")
      (node (ref "D6") (pin "2") (pinfunction "In2_2") (pintype "input"))
      (node (ref "D6") (pin "5") (pinfunction "In2_5") (pintype "input"))
      (node (ref "D6") (pin "9") (pinfunction "In1_9") (pintype "input"))
    )
    (net (code "55") (name "Net-(D6D-Out)") (class "Default")
      (node (ref "D6") (pin "11") (pinfunction "Out_11") (pintype "output"))
      (node (ref "D9") (pin "14") (pinfunction "Clock_14") (pintype "input"))
    )
    (net (code "56") (name "Net-(D9A-\"0\")") (class "Default")
      (node (ref "D9") (pin "3") (pinfunction "\"0\"_3") (pintype "output"))
      (node (ref "R9") (pin "0") (pinfunction "1_0") (pintype "passive"))
    )
    (net (code "57") (name "Net-(D9A-\"1\")") (class "Default")
      (node (ref "D9") (pin "2") (pinfunction "\"1\"_2") (pintype "output"))
      (node (ref "R10") (pin "0") (pinfunction "1_0") (pintype "passive"))
    )
    (net (code "58") (name "Net-(D9A-\"2\")") (class "Default")
      (node (ref "D9") (pin "4") (pinfunction "\"2\"_4") (pintype "output"))
      (node (ref "R11") (pin "0") (pinfunction "1_0") (pintype "passive"))
    )
    (net (code "59") (name "Net-(D9A-\"3\")") (class "Default")
      (node (ref "D9") (pin "7") (pinfunction "\"3\"_7") (pintype "output"))
      (node (ref "R13") (pin "0") (pinfunction "1_0") (pintype "passive"))
    )
    (net (code "60") (name "Net-(D9A-\"4\")") (class "Default")
      (node (ref "D9") (pin "10") (pinfunction "\"4\"_10") (pintype "output"))
      (node (ref "R14") (pin "0") (pinfunction "1_0") (pintype "passive"))
    )
    (net (code "61") (name "Net-(D9A-\"5\")") (class "Default")
      (node (ref "D9") (pin "1") (pinfunction "\"5\"_1") (pintype "output"))
      (node (ref "R16") (pin "0") (pinfunction "1_0") (pintype "passive"))
    )
    (net (code "62") (name "Net-(D9A-\"6\")") (class "Default")
      (node (ref "D9") (pin "5") (pinfunction "\"6\"_5") (pintype "output"))
      (node (ref "R17") (pin "0") (pinfunction "1_0") (pintype "passive"))
    )
    (net (code "63") (name "Net-(D9A-\"7\")") (class "Default")
      (node (ref "D9") (pin "6") (pinfunction "\"7\"_6") (pintype "output"))
      (node (ref "R19") (pin "0") (pinfunction "1_0") (pintype "passive"))
    )
    (net (code "64") (name "Net-(D9A-\"9\")") (class "Default")
      (node (ref "D9") (pin "11") (pinfunction "\"9\"_11") (pintype "output"))
      (node (ref "R21") (pin "0") (pinfunction "1_0") (pintype "passive"))
    )
    (net (code "65") (name "Net-(D11-E)") (class "Default")
      (node (ref "D11") (pin "7") (pinfunction "E_7") (pintype "input"))
      (node (ref "D6") (pin "3") (pinfunction "Out_3") (pintype "output"))
    )
    (net (code "66") (name "Net-(D12-E)") (class "Default")
      (node (ref "D12") (pin "7") (pinfunction "E_7") (pintype "input"))
      (node (ref "D6") (pin "6") (pinfunction "Out_6") (pintype "output"))
    )
    (net (code "67") (name "Net-(D13-E)") (class "Default")
      (node (ref "D13") (pin "7") (pinfunction "E_7") (pintype "input"))
      (node (ref "D6") (pin "8") (pinfunction "Out_8") (pintype "output"))
    )
    (net (code "68") (name "Net-(R9-Pad1)") (class "Default")
      (node (ref "R9") (pin "1") (pinfunction "1_1") (pintype "passive"))
      (node (ref "VD16") (pin "A") (pinfunction "A_A") (pintype "passive"))
    )
    (net (code "69") (name "Net-(R10-Pad1)") (class "Default")
      (node (ref "R10") (pin "1") (pinfunction "1_1") (pintype "passive"))
      (node (ref "VD15") (pin "A") (pinfunction "A_A") (pintype "passive"))
    )
    (net (code "70") (name "Net-(R11-Pad1)") (class "Default")
      (node (ref "R11") (pin "1") (pinfunction "1_1") (pintype "passive"))
      (node (ref "VD14") (pin "A") (pinfunction "A_A") (pintype "passive"))
    )
    (net (code "71") (name "Net-(R12-1-Pad0)") (class "Default")
      (node (ref "R12") (pin "0") (pinfunction "1_0") (pintype "passive"))
      (node (ref "VD4") (pin "K") (pinfunction "K_K") (pintype "passive"))
    )
    (net (code "72") (name "Net-(R13-Pad1)") (class "Default")
      (node (ref "R13") (pin "1") (pinfunction "1_1") (pintype "passive"))
      (node (ref "VD13") (pin "A") (pinfunction "A_A") (pintype "passive"))
    )
    (net (code "73") (name "Net-(R14-Pad1)") (class "Default")
      (node (ref "R14") (pin "1") (pinfunction "1_1") (pintype "passive"))
      (node (ref "VD12") (pin "A") (pinfunction "A_A") (pintype "passive"))
    )
    (net (code "74") (name "Net-(R15-1-Pad0)") (class "Default")
      (node (ref "R15") (pin "0") (pinfunction "1_0") (pintype "passive"))
      (node (ref "VD5") (pin "K") (pinfunction "K_K") (pintype "passive"))
    )
    (net (code "75") (name "Net-(R16-Pad1)") (class "Default")
      (node (ref "R16") (pin "1") (pinfunction "1_1") (pintype "passive"))
      (node (ref "VD11") (pin "A") (pinfunction "A_A") (pintype "passive"))
    )
    (net (code "76") (name "Net-(R17-Pad1)") (class "Default")
      (node (ref "R17") (pin "1") (pinfunction "1_1") (pintype "passive"))
      (node (ref "VD10") (pin "A") (pinfunction "A_A") (pintype "passive"))
    )
    (net (code "77") (name "Net-(R18-1-Pad0)") (class "Default")
      (node (ref "R18") (pin "0") (pinfunction "1_0") (pintype "passive"))
      (node (ref "VD6") (pin "K") (pinfunction "K_K") (pintype "passive"))
    )
    (net (code "78") (name "Net-(R19-Pad1)") (class "Default")
      (node (ref "R19") (pin "1") (pinfunction "1_1") (pintype "passive"))
      (node (ref "VD9") (pin "A") (pinfunction "A_A") (pintype "passive"))
    )
    (net (code "79") (name "Net-(R20-1-Pad0)") (class "Default")
      (node (ref "R20") (pin "0") (pinfunction "1_0") (pintype "passive"))
      (node (ref "VD7") (pin "K") (pinfunction "K_K") (pintype "passive"))
    )
    (net (code "80") (name "Net-(R21-Pad1)") (class "Default")
      (node (ref "R21") (pin "1") (pinfunction "1_1") (pintype "passive"))
      (node (ref "VD8") (pin "A") (pinfunction "A_A") (pintype "passive"))
    )
    (net (code "81") (name "Reset") (class "Default")
      (node (ref "D1") (pin "15") (pinfunction "Reset_15") (pintype "input"))
      (node (ref "D2") (pin "15") (pinfunction "Reset_15") (pintype "input"))
      (node (ref "D8") (pin "15") (pinfunction "Reset_15") (pintype "input"))
      (node (ref "D9") (pin "15") (pinfunction "Reset_15") (pintype "input"))
    )
    (net (code "82") (name "S0") (class "Default")
      (node (ref "D11") (pin "11") (pinfunction "S0_11") (pintype "input"))
      (node (ref "D12") (pin "11") (pinfunction "S0_11") (pintype "input"))
      (node (ref "D13") (pin "11") (pinfunction "S0_11") (pintype "input"))
    )
    (net (code "83") (name "S1") (class "Default")
      (node (ref "D11") (pin "10") (pinfunction "S1_10") (pintype "input"))
      (node (ref "D12") (pin "10") (pinfunction "S1_10") (pintype "input"))
      (node (ref "D13") (pin "10") (pinfunction "S1_10") (pintype "input"))
    )
    (net (code "84") (name "S2") (class "Default")
      (node (ref "D11") (pin "9") (pinfunction "S2_9") (pintype "input"))
      (node (ref "D12") (pin "9") (pinfunction "S2_9") (pintype "input"))
      (node (ref "D13") (pin "9") (pinfunction "S2_9") (pintype "input"))
    )
    (net (code "85") (name "unconnected-(D1A-\"8\"-Pad9)") (class "Default")
      (node (ref "D1") (pin "9") (pinfunction "\"8\"_9") (pintype "output"))
    )
    (net (code "86") (name "unconnected-(D1A-\"9\"-Pad11)") (class "Default")
      (node (ref "D1") (pin "11") (pinfunction "\"9\"_11") (pintype "output"))
    )
    (net (code "87") (name "unconnected-(D9A-\"8\"-Pad9)") (class "Default")
      (node (ref "D9") (pin "9") (pinfunction "\"8\"_9") (pintype "output"))
    )
    (net (code "88") (name "unconnected-(D9A-Carry-Pad12)") (class "Default")
      (node (ref "D9") (pin "12") (pinfunction "Carry_12") (pintype "output"))
    )
  )
)
